# DM1097_HDMI.net
KiCad netlist of a schematic drawn in Altium Designer
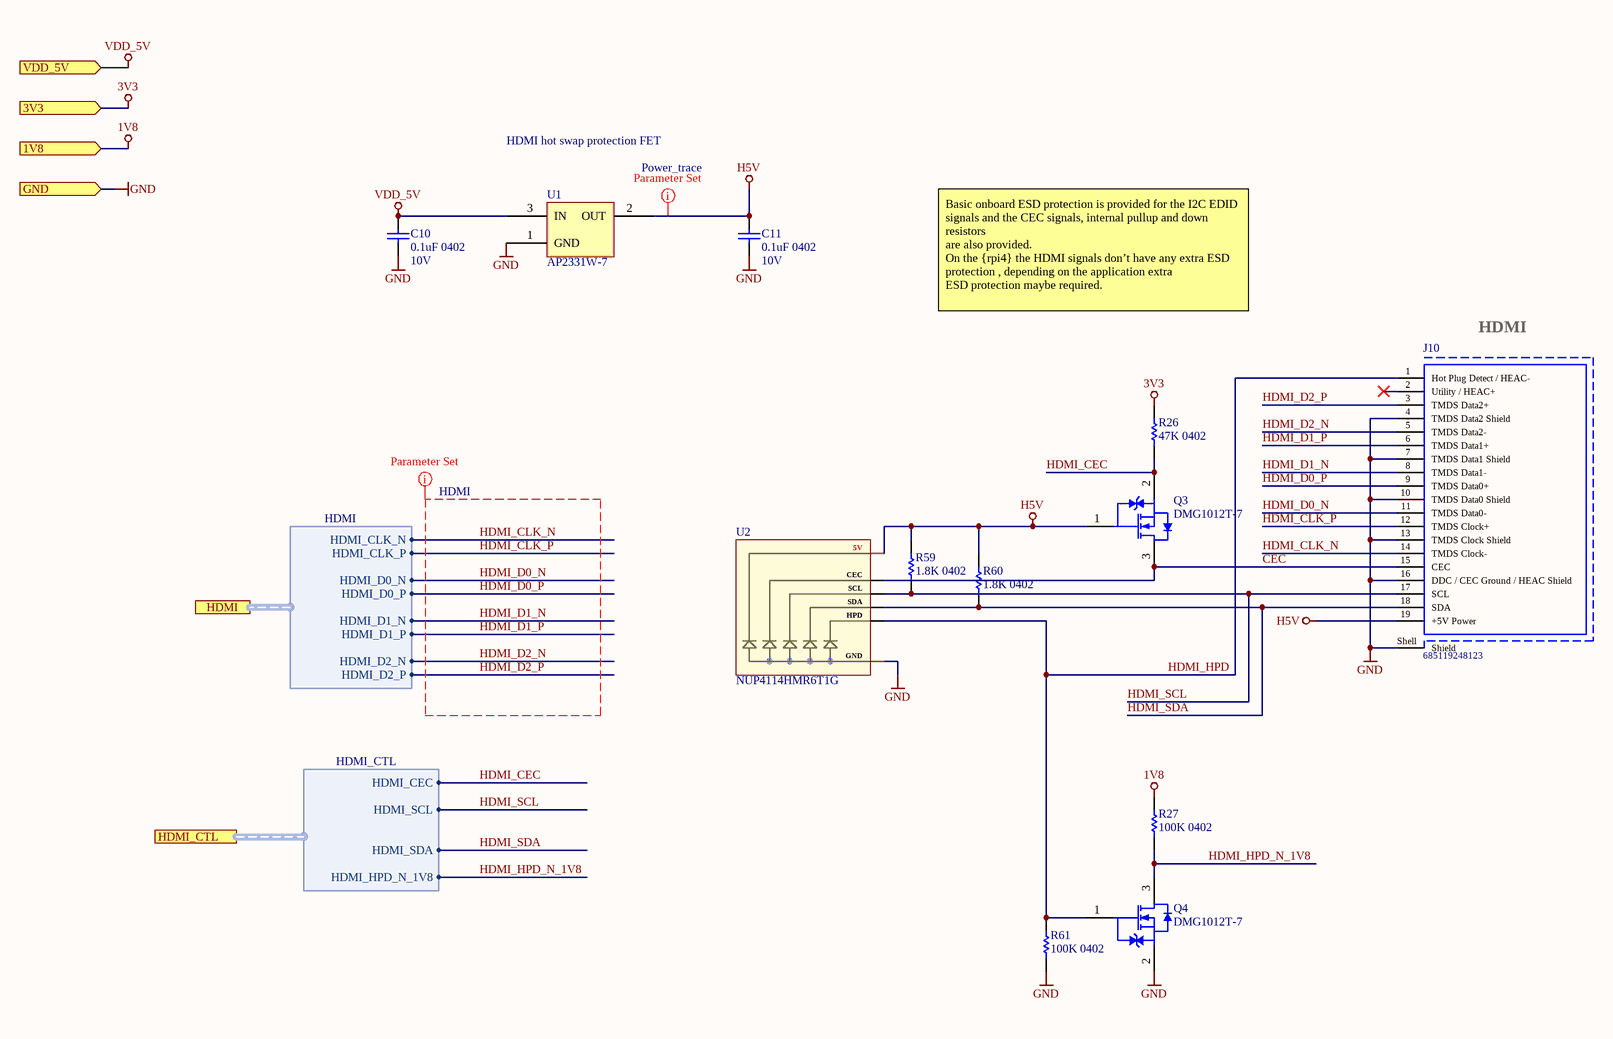
[diagram p0: DM1097_HDMI.SchDoc]

(export (version "E")
  (design (tool "Eeschema 10.0.6"))
  (components
    (comp (ref "C10")
      (value "0.1uF 0402")
      (footprint "CAP_Altium_Vault_Generic:CAPC0402(1005)70_N")
      (description "CAP CER 0.1UF 10V X7R 0402 5%")
      (fields (field (name "TOLERANCE") "5%") (field (name "VOLTAGE RATING") "10V"))
      (libsource (lib "LuxonisMaster") (part "GRM155R71A104JA01D"))
    )
    (comp (ref "C11")
      (value "0.1uF 0402")
      (footprint "CAP_Altium_Vault_Generic:CAPC0402(1005)70_N")
      (description "CAP CER 0.1UF 10V X7R 0402 5%")
      (fields (field (name "TOLERANCE") "5%") (field (name "VOLTAGE RATING") "10V"))
      (libsource (lib "LuxonisMaster") (part "GRM155R71A104JA01D"))
    )
    (comp (ref "J10")
      (value "685119248123")
      (footprint "685119248123")
      (description "Micro HDMI Type D Receptacle WR-COM, Horizontal, SMT")
      (fields (field (name "MANUFACTURER") "Wurth Electronics") (field (name "PUBLISHER") "WurthElektronik"))
      (libsource (lib "DM1097_R1M1E1") (part "685119248123"))
    )
    (comp (ref "Q3")
      (value "DMG1012T-7")
      (footprint "LuxonisMaster:DMG1012T-7")
      (description "MOSFET N-CH 20V 630MA SOT-523")
      (libsource (lib "LuxonisMaster") (part "DMG1012T-7"))
    )
    (comp (ref "Q4")
      (value "DMG1012T-7")
      (footprint "LuxonisMaster:DMG1012T-7")
      (description "MOSFET N-CH 20V 630MA SOT-523")
      (libsource (lib "LuxonisMaster") (part "DMG1012T-7"))
    )
    (comp (ref "R26")
      (value "47K 0402")
      (footprint "RES_Altium_Vault_Generic:RESC0402(1005)_N")
      (description "RES SMD 47K OHM 1% 1/16W 0402")
      (fields (field (name "TOLERANCE") "1%"))
      (libsource (lib "LuxonisMaster") (part "RC0402FR-0747KL"))
    )
    (comp (ref "R27")
      (value "100K 0402")
      (footprint "RES_Altium_Vault_Generic:RESC0402(1005)_N")
      (description "RES SMD 100K OHM 1% 1/16W 0402")
      (fields (field (name "TOLERANCE") "1%"))
      (libsource (lib "LuxonisMaster") (part "RC0402FR-07100KL"))
    )
    (comp (ref "R59")
      (value "1.8K 0402")
      (footprint "RES_Altium_Vault_Generic:RESC0402(1005)_L")
      (description "RES SMD 1.8K OHM 1% 1/16W 0402")
      (fields (field (name "TOLERANCE") "1%"))
      (libsource (lib "LuxonisMaster") (part "RC0402FR-071K8L"))
    )
    (comp (ref "R60")
      (value "1.8K 0402")
      (footprint "RES_Altium_Vault_Generic:RESC0402(1005)_L")
      (description "RES SMD 1.8K OHM 1% 1/16W 0402")
      (fields (field (name "TOLERANCE") "1%"))
      (libsource (lib "LuxonisMaster") (part "RC0402FR-071K8L"))
    )
    (comp (ref "R61")
      (value "100K 0402")
      (footprint "RES_Altium_Vault_Generic:RESC0402(1005)_N")
      (description "RES SMD 100K OHM 1% 1/16W 0402")
      (fields (field (name "TOLERANCE") "1%"))
      (libsource (lib "LuxonisMaster") (part "RC0402FR-07100KL"))
    )
    (comp (ref "U1")
      (value "AP2331W-7")
      (footprint "LuxonisMaster:AP2331W-7")
      (description "LOAD SWITCH SC59")
      (fields (field (name "VOLTAGE") "5.2V"))
      (libsource (lib "LuxonisMaster") (part "AP2331W-7"))
    )
    (comp (ref "U2")
      (value "NUP4114HMR6T1G")
      (footprint "SOT23-6")
      (description "TVS DIODE 3VWM 9WLCSP")
      (libsource (lib "DM1097_SchLib") (part "NUP4114"))
    )
  )
  (nets
    (net (code "3") (name "/CEC") (class "Default")
      (node (ref "J10") (pin "15") (pinfunction "CEC_15") (pintype "passive"))
      (node (ref "Q3") (pin "3") (pinfunction "3_3") (pintype "passive"))
      (node (ref "U2") (pin "1") (pinfunction "A2_1") (pintype "passive"))
    )
    (net (code "4") (name "/HDMI_CEC") (class "Default")
      (node (ref "Q3") (pin "2") (pinfunction "2_2") (pintype "passive"))
      (node (ref "R26") (pin "1") (pinfunction "1_1") (pintype "passive"))
    )
    (net (code "5") (name "/HDMI_CLK_N") (class "Default")
      (node (ref "J10") (pin "14") (pinfunction "TMDS_Clock-_14") (pintype "passive"))
    )
    (net (code "6") (name "/HDMI_CLK_P") (class "Default")
      (node (ref "J10") (pin "12") (pinfunction "TMDS_Clock+_12") (pintype "passive"))
    )
    (net (code "7") (name "/HDMI_D0_N") (class "Default")
      (node (ref "J10") (pin "11") (pinfunction "TMDS_Data0-_11") (pintype "passive"))
    )
    (net (code "8") (name "/HDMI_D0_P") (class "Default")
      (node (ref "J10") (pin "9") (pinfunction "TMDS_Data0+_9") (pintype "passive"))
    )
    (net (code "9") (name "/HDMI_D1_N") (class "Default")
      (node (ref "J10") (pin "8") (pinfunction "TMDS_Data1-_8") (pintype "passive"))
    )
    (net (code "10") (name "/HDMI_D1_P") (class "Default")
      (node (ref "J10") (pin "6") (pinfunction "TMDS_Data1+_6") (pintype "passive"))
    )
    (net (code "11") (name "/HDMI_D2_N") (class "Default")
      (node (ref "J10") (pin "5") (pinfunction "TMDS_Data2-_5") (pintype "passive"))
    )
    (net (code "12") (name "/HDMI_D2_P") (class "Default")
      (node (ref "J10") (pin "3") (pinfunction "TMDS_Data2+_3") (pintype "passive"))
    )
    (net (code "13") (name "/HDMI_HPD") (class "Default")
      (node (ref "J10") (pin "1") (pinfunction "Hot_Plug_Detect_/_HEAC-_1") (pintype "passive"))
      (node (ref "Q4") (pin "1") (pinfunction "1_1") (pintype "passive"))
      (node (ref "R61") (pin "2") (pinfunction "2_2") (pintype "passive"))
      (node (ref "U2") (pin "6") (pinfunction "1_6") (pintype "passive"))
    )
    (net (code "14") (name "/HDMI_HPD_N_1V8") (class "Default")
      (node (ref "Q4") (pin "3") (pinfunction "3_3") (pintype "passive"))
      (node (ref "R27") (pin "1") (pinfunction "1_1") (pintype "passive"))
    )
    (net (code "15") (name "/HDMI_SCL") (class "Default")
      (node (ref "J10") (pin "17") (pinfunction "SCL_17") (pintype "passive"))
      (node (ref "R59") (pin "1") (pinfunction "1_1") (pintype "passive"))
      (node (ref "U2") (pin "3") (pinfunction "A3_3") (pintype "passive"))
    )
    (net (code "16") (name "/HDMI_SDA") (class "Default")
      (node (ref "J10") (pin "18") (pinfunction "SDA_18") (pintype "passive"))
      (node (ref "R60") (pin "1") (pinfunction "1_1") (pintype "passive"))
      (node (ref "U2") (pin "4") (pinfunction "B3_4") (pintype "passive"))
    )
    (net (code "19") (name "1V8") (class "Default")
      (node (ref "R27") (pin "2") (pinfunction "2_2") (pintype "passive"))
    )
    (net (code "20") (name "3V3") (class "Default")
      (node (ref "R26") (pin "2") (pinfunction "2_2") (pintype "passive"))
    )
    (net (code "21") (name "GND") (class "Default")
      (node (ref "C10") (pin "1") (pinfunction "1_1") (pintype "passive"))
      (node (ref "C11") (pin "1") (pinfunction "1_1") (pintype "passive"))
      (node (ref "J10") (pin "10") (pinfunction "TMDS_Data0_Shield_10") (pintype "passive"))
      (node (ref "J10") (pin "13") (pinfunction "TMDS_Clock_Shield_13") (pintype "passive"))
      (node (ref "J10") (pin "16") (pinfunction "DDC_/_CEC_Ground_/_HEAC_Shield_16") (pintype "passive"))
      (node (ref "J10") (pin "4") (pinfunction "TMDS_Data2_Shield_4") (pintype "passive"))
      (node (ref "J10") (pin "7") (pinfunction "TMDS_Data1_Shield_7") (pintype "passive"))
      (node (ref "J10") (pin "Shell") (pinfunction "Shield_Shell") (pintype "passive"))
      (node (ref "Q4") (pin "2") (pinfunction "2_2") (pintype "passive"))
      (node (ref "R61") (pin "1") (pinfunction "1_1") (pintype "passive"))
      (node (ref "U1") (pin "1") (pinfunction "GND_1") (pintype "passive"))
      (node (ref "U2") (pin "2") (pinfunction "B2_2") (pintype "passive"))
    )
    (net (code "22") (name "H5V") (class "Default")
      (node (ref "C11") (pin "2") (pinfunction "2_2") (pintype "passive"))
      (node (ref "J10") (pin "19") (pinfunction "+5V_Power_19") (pintype "passive"))
      (node (ref "Q3") (pin "1") (pinfunction "1_1") (pintype "passive"))
      (node (ref "R59") (pin "2") (pinfunction "2_2") (pintype "passive"))
      (node (ref "R60") (pin "2") (pinfunction "2_2") (pintype "passive"))
      (node (ref "U1") (pin "2") (pinfunction "OUT_2") (pintype "passive"))
      (node (ref "U2") (pin "5") (pinfunction "A1_5") (pintype "passive"))
    )
    (net (code "23") (name "VDD_5V") (class "Default")
      (node (ref "C10") (pin "2") (pinfunction "2_2") (pintype "passive"))
      (node (ref "U1") (pin "3") (pinfunction "IN_3") (pintype "passive"))
    )
    (net (code "24") (name "unconnected-(J10-Utility_{slash}_HEAC+-Pad2)") (class "Default")
      (node (ref "J10") (pin "2") (pinfunction "Utility_/_HEAC+_2") (pintype "passive+no_connect"))
    )
  )
)
